# Pin-with-a-screen-3v3.net
KiCad netlist of a schematic drawn in EAGLE
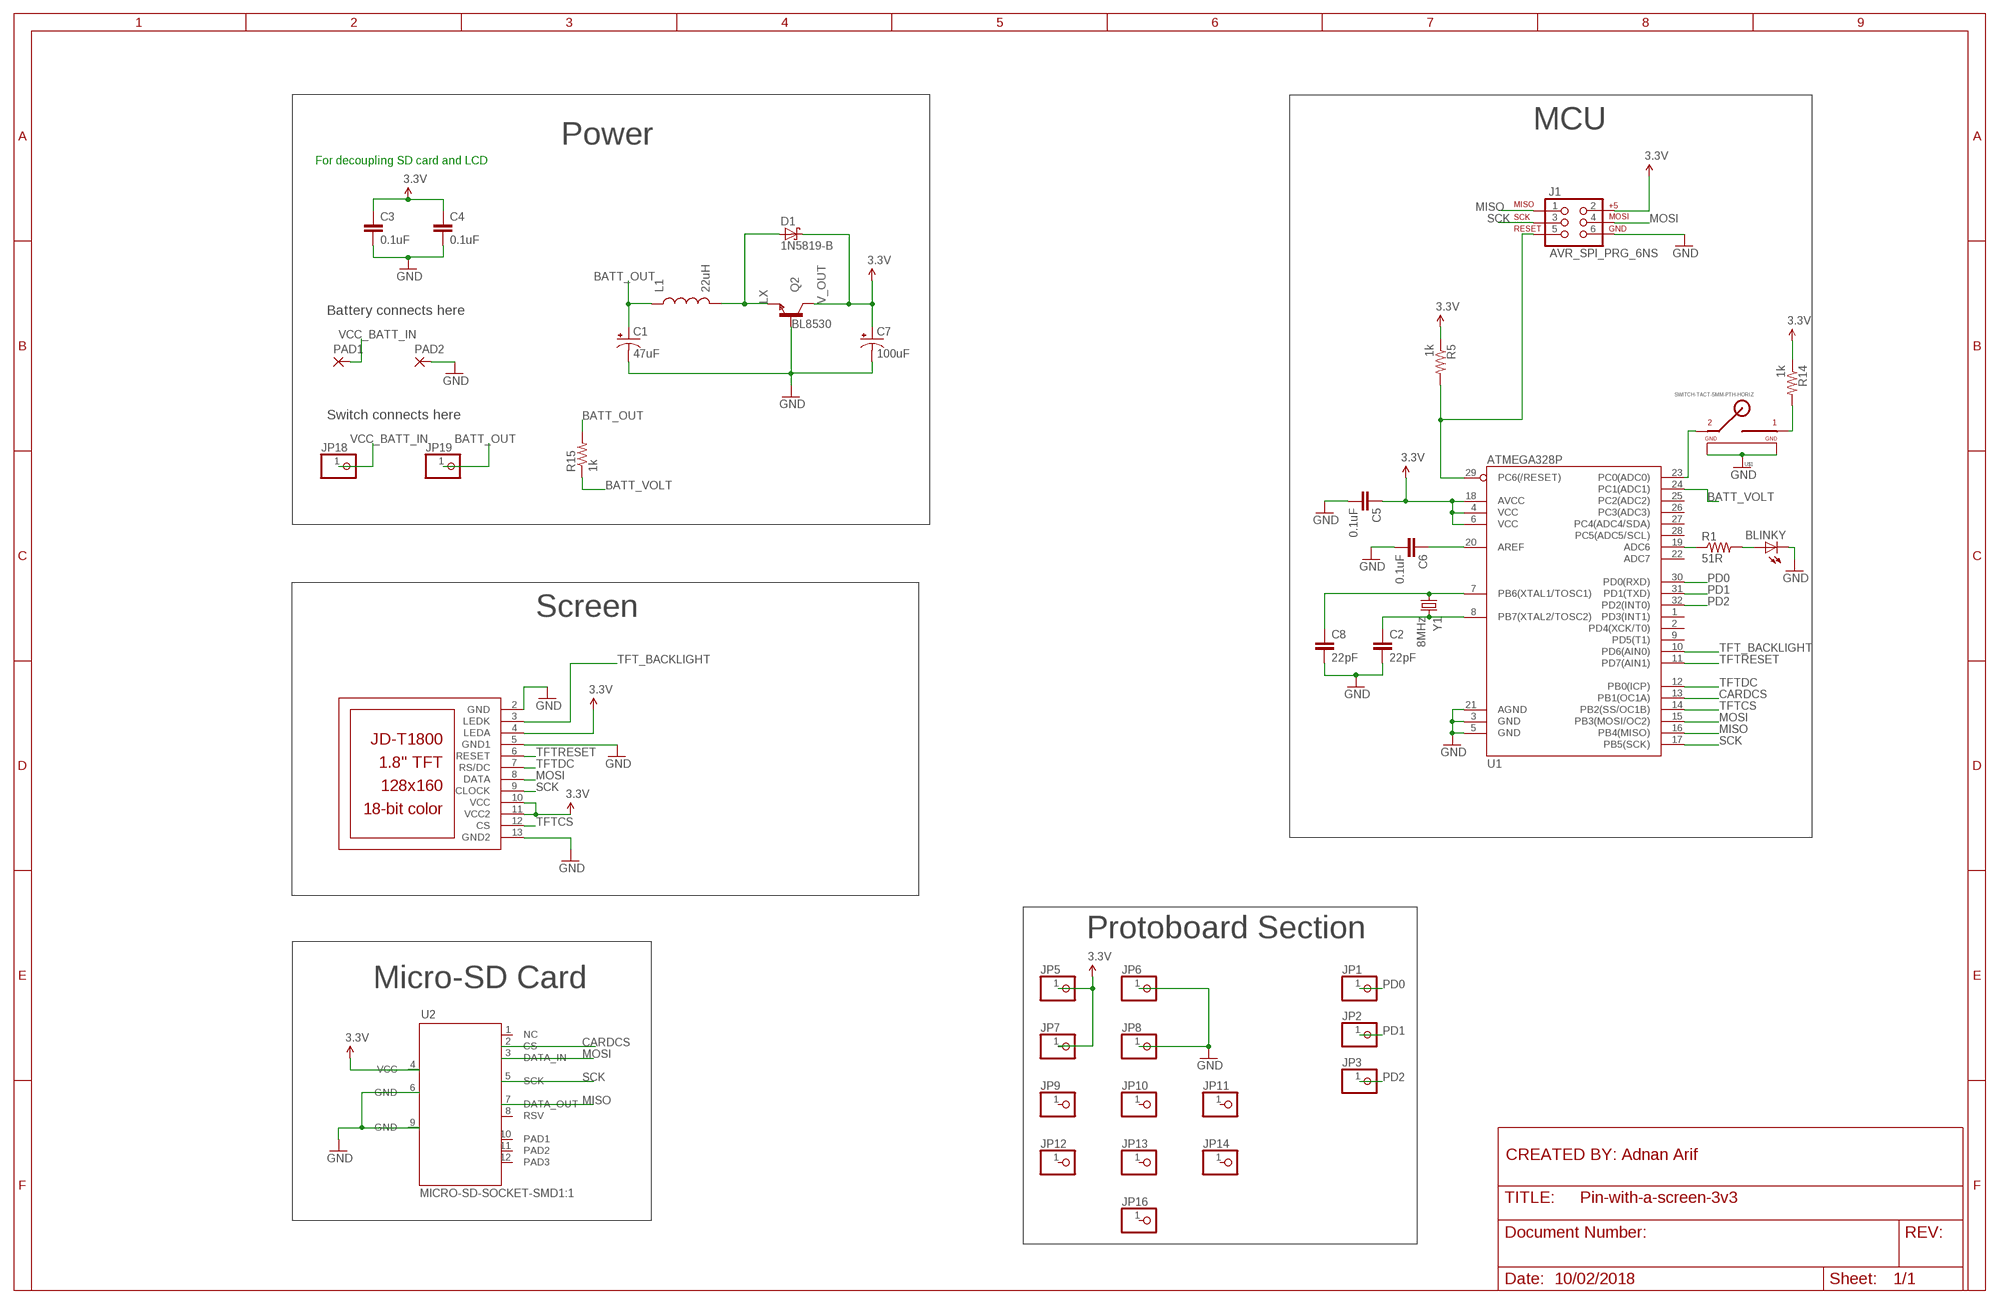
[diagram p0: schematic, sheet 1]

(export (version "E")
  (design (tool "Eeschema 10.0.6"))
  (components
    (comp (ref "BLINKY")
      (value "Red")
      (footprint "eagle-import:LED-0603")
      (libsource (lib "eagle-import") (part "LED0603"))
    )
    (comp (ref "C1")
      (value "47uF")
      (footprint "eagle-import:EIA3528-KIT")
      (libsource (lib "eagle-import") (part "CAP_POL3528-KIT"))
    )
    (comp (ref "C2")
      (value "22pF")
      (footprint "eagle-import:0603-CAP")
      (libsource (lib "eagle-import") (part "CAP0603-CAP"))
    )
    (comp (ref "C3")
      (value "0.1uF")
      (footprint "eagle-import:0603-CAP")
      (libsource (lib "eagle-import") (part "CAP0603-CAP"))
    )
    (comp (ref "C4")
      (value "0.1uF")
      (footprint "eagle-import:0603-CAP")
      (libsource (lib "eagle-import") (part "CAP0603-CAP"))
    )
    (comp (ref "C5")
      (value "0.1uF")
      (footprint "eagle-import:0603-CAP")
      (libsource (lib "eagle-import") (part "CAP0603-CAP"))
    )
    (comp (ref "C6")
      (value "0.1uF")
      (footprint "eagle-import:0603-CAP")
      (libsource (lib "eagle-import") (part "CAP0603-CAP"))
    )
    (comp (ref "C7")
      (value "100uF")
      (footprint "eagle-import:EIA3528-KIT")
      (libsource (lib "eagle-import") (part "CAP_POL3528-KIT"))
    )
    (comp (ref "C8")
      (value "22pF")
      (footprint "eagle-import:0603-CAP")
      (libsource (lib "eagle-import") (part "CAP0603-CAP"))
    )
    (comp (ref "D1")
      (value "1N5819-B")
      (footprint "eagle-import:DO41-7.6")
      (libsource (lib "eagle-import") (part "1N5819-B"))
    )
    (comp (ref "J1")
      (value "AVR_SPI_PRG_6NS")
      (footprint "eagle-import:2X3-NS")
      (libsource (lib "eagle-import") (part "AVR_SPI_PRG_6NS"))
    )
    (comp (ref "JP1")
      (value "PINHD-1X1")
      (footprint "eagle-import:1X01")
      (libsource (lib "eagle-import") (part "PINHD-1X1"))
    )
    (comp (ref "JP2")
      (value "PINHD-1X1")
      (footprint "eagle-import:1X01")
      (libsource (lib "eagle-import") (part "PINHD-1X1"))
    )
    (comp (ref "JP3")
      (value "PINHD-1X1")
      (footprint "eagle-import:1X01")
      (libsource (lib "eagle-import") (part "PINHD-1X1"))
    )
    (comp (ref "JP5")
      (value "PINHD-1X1")
      (footprint "eagle-import:1X01")
      (libsource (lib "eagle-import") (part "PINHD-1X1"))
    )
    (comp (ref "JP6")
      (value "PINHD-1X1")
      (footprint "eagle-import:1X01")
      (libsource (lib "eagle-import") (part "PINHD-1X1"))
    )
    (comp (ref "JP7")
      (value "PINHD-1X1")
      (footprint "eagle-import:1X01")
      (libsource (lib "eagle-import") (part "PINHD-1X1"))
    )
    (comp (ref "JP8")
      (value "PINHD-1X1")
      (footprint "eagle-import:1X01")
      (libsource (lib "eagle-import") (part "PINHD-1X1"))
    )
    (comp (ref "JP9")
      (value "PINHD-1X1")
      (footprint "eagle-import:1X01")
      (libsource (lib "eagle-import") (part "PINHD-1X1"))
    )
    (comp (ref "JP10")
      (value "PINHD-1X1")
      (footprint "eagle-import:1X01")
      (libsource (lib "eagle-import") (part "PINHD-1X1"))
    )
    (comp (ref "JP11")
      (value "PINHD-1X1")
      (footprint "eagle-import:1X01")
      (libsource (lib "eagle-import") (part "PINHD-1X1"))
    )
    (comp (ref "JP12")
      (value "PINHD-1X1")
      (footprint "eagle-import:1X01")
      (libsource (lib "eagle-import") (part "PINHD-1X1"))
    )
    (comp (ref "JP13")
      (value "PINHD-1X1")
      (footprint "eagle-import:1X01")
      (libsource (lib "eagle-import") (part "PINHD-1X1"))
    )
    (comp (ref "JP14")
      (value "PINHD-1X1")
      (footprint "eagle-import:1X01")
      (libsource (lib "eagle-import") (part "PINHD-1X1"))
    )
    (comp (ref "JP16")
      (value "PINHD-1X1")
      (footprint "eagle-import:1X01")
      (libsource (lib "eagle-import") (part "PINHD-1X1"))
    )
    (comp (ref "JP18")
      (value "PINHD-1X1")
      (footprint "eagle-import:1X01")
      (libsource (lib "eagle-import") (part "PINHD-1X1"))
    )
    (comp (ref "JP19")
      (value "PINHD-1X1")
      (footprint "eagle-import:1X01")
      (libsource (lib "eagle-import") (part "PINHD-1X1"))
    )
    (comp (ref "L1")
      (value "22uH")
      (footprint "eagle-import:0603")
      (libsource (lib "eagle-import") (part "INDUCTOR0603"))
    )
    (comp (ref "LCD2")
      (value "JD-T1800")
      (footprint "eagle-import:JD-T1800")
      (libsource (lib "eagle-import") (part "JD-T1800"))
    )
    (comp (ref "PAD1")
      (value "2,15/1,0")
      (footprint "eagle-import:2,15_1,0")
      (libsource (lib "eagle-import") (part "2,15/1,0"))
    )
    (comp (ref "PAD2")
      (value "2,15/1,0")
      (footprint "eagle-import:2,15_1,0")
      (libsource (lib "eagle-import") (part "2,15/1,0"))
    )
    (comp (ref "Q2")
      (value "BL8530")
      (footprint "eagle-import:SOT89")
      (libsource (lib "eagle-import") (part "TRANSISTOR_NPNSOT89"))
    )
    (comp (ref "R1")
      (value "51R")
      (footprint "eagle-import:0603-RES")
      (libsource (lib "eagle-import") (part "RESISTOR0603-RES"))
    )
    (comp (ref "R5")
      (value "1k")
      (footprint "eagle-import:0603-RES")
      (libsource (lib "eagle-import") (part "RESISTOR0603-RES"))
    )
    (comp (ref "R14")
      (value "1k")
      (footprint "eagle-import:0603-RES")
      (libsource (lib "eagle-import") (part "RESISTOR0603-RES"))
    )
    (comp (ref "R15")
      (value "1k")
      (footprint "eagle-import:0603-RES")
      (libsource (lib "eagle-import") (part "RESISTOR0603-RES"))
    )
    (comp (ref "U$1")
      (value "SWITCH-TACT-5MM-PTH-HORIZ")
      (footprint "eagle-import:5MM-PTH")
      (libsource (lib "eagle-import") (part "SWITCH-TACT-5MM-PTH-HORIZ"))
    )
    (comp (ref "U1")
      (value "ATMEGA328P")
      (footprint "eagle-import:TQFP32-08")
      (libsource (lib "eagle-import") (part "ATMEGA328_SMT"))
    )
    (comp (ref "U2")
      (value "MICRO-SD-SOCKET-SMD1:1")
      (footprint "eagle-import:MICRO-SD-SOCKET-SMD-1_1")
      (libsource (lib "eagle-import") (part "MICRO-SD-SOCKET-SMD1{colon}1"))
    )
    (comp (ref "Y1")
      (value "8MHz")
      (footprint "eagle-import:HC49UP")
      (libsource (lib "eagle-import") (part "CRYSTALSMD"))
    )
  )
  (nets
    (net (code "1") (name "/BATT_OUT") (class "Default")
      (node (ref "C1") (pin "A") (pinfunction "+_A") (pintype "passive"))
      (node (ref "JP19") (pin "1") (pinfunction "1_1") (pintype "passive"))
      (node (ref "L1") (pin "1") (pinfunction "1_1") (pintype "passive"))
      (node (ref "R15") (pin "2") (pinfunction "2_2") (pintype "passive"))
    )
    (net (code "2") (name "/BATT_VOLT") (class "Default")
      (node (ref "R15") (pin "1") (pinfunction "1_1") (pintype "passive"))
      (node (ref "U1") (pin "24") (pinfunction "PC1(ADC1)_24") (pintype "bidirectional"))
    )
    (net (code "3") (name "/CARDCS") (class "Default")
      (node (ref "U1") (pin "13") (pinfunction "PB1(OC1A)_13") (pintype "bidirectional"))
      (node (ref "U2") (pin "2") (pinfunction "CS_2") (pintype "input"))
    )
    (net (code "4") (name "/LX") (class "Default")
      (node (ref "D1") (pin "A") (pinfunction "A_A") (pintype "passive"))
      (node (ref "L1") (pin "2") (pinfunction "2_2") (pintype "passive"))
      (node (ref "Q2") (pin "3") (pinfunction "E_3") (pintype "passive"))
    )
    (net (code "5") (name "/MISO") (class "Default")
      (node (ref "J1") (pin "1") (pinfunction "1_1") (pintype "passive"))
      (node (ref "U1") (pin "16") (pinfunction "PB4(MISO)_16") (pintype "bidirectional"))
      (node (ref "U2") (pin "7") (pinfunction "DATA_OUT_7") (pintype "output"))
    )
    (net (code "6") (name "/MOSI") (class "Default")
      (node (ref "J1") (pin "4") (pinfunction "4_4") (pintype "passive"))
      (node (ref "LCD2") (pin "8") (pinfunction "DATA_8") (pintype "bidirectional"))
      (node (ref "U1") (pin "15") (pinfunction "PB3(MOSI/OC2)_15") (pintype "bidirectional"))
      (node (ref "U2") (pin "3") (pinfunction "DATA_IN_3") (pintype "input"))
    )
    (net (code "7") (name "/PD0") (class "Default")
      (node (ref "JP1") (pin "1") (pinfunction "1_1") (pintype "passive"))
      (node (ref "U1") (pin "30") (pinfunction "PD0(RXD)_30") (pintype "bidirectional"))
    )
    (net (code "8") (name "/PD1") (class "Default")
      (node (ref "JP2") (pin "1") (pinfunction "1_1") (pintype "passive"))
      (node (ref "U1") (pin "31") (pinfunction "PD1(TXD)_31") (pintype "bidirectional"))
    )
    (net (code "9") (name "/PD2") (class "Default")
      (node (ref "JP3") (pin "1") (pinfunction "1_1") (pintype "passive"))
      (node (ref "U1") (pin "32") (pinfunction "PD2(INT0)_32") (pintype "bidirectional"))
    )
    (net (code "10") (name "/SCK") (class "Default")
      (node (ref "J1") (pin "3") (pinfunction "3_3") (pintype "passive"))
      (node (ref "LCD2") (pin "9") (pinfunction "CLOCK_9") (pintype "input"))
      (node (ref "U1") (pin "17") (pinfunction "PB5(SCK)_17") (pintype "bidirectional"))
      (node (ref "U2") (pin "5") (pinfunction "SCK_5") (pintype "input"))
    )
    (net (code "11") (name "/TFTCS") (class "Default")
      (node (ref "LCD2") (pin "12") (pinfunction "CS_12") (pintype "input"))
      (node (ref "U1") (pin "14") (pinfunction "PB2(SS/OC1B)_14") (pintype "bidirectional"))
    )
    (net (code "12") (name "/TFTDC") (class "Default")
      (node (ref "LCD2") (pin "7") (pinfunction "RS/DC_7") (pintype "input"))
      (node (ref "U1") (pin "12") (pinfunction "PB0(ICP)_12") (pintype "bidirectional"))
    )
    (net (code "13") (name "/TFTRESET") (class "Default")
      (node (ref "LCD2") (pin "6") (pinfunction "RESET_6") (pintype "input"))
      (node (ref "U1") (pin "11") (pinfunction "PD7(AIN1)_11") (pintype "bidirectional"))
    )
    (net (code "14") (name "/TFT_BACKLIGHT") (class "Default")
      (node (ref "LCD2") (pin "3") (pinfunction "LEDK_3") (pintype "input"))
      (node (ref "U1") (pin "10") (pinfunction "PD6(AIN0)_10") (pintype "bidirectional"))
    )
    (net (code "15") (name "/VCC_BATT_IN") (class "Default")
      (node (ref "JP18") (pin "1") (pinfunction "1_1") (pintype "passive"))
      (node (ref "PAD1") (pin "1") (pinfunction "P_1") (pintype "passive"))
    )
    (net (code "16") (name "3.3V") (class "Default")
      (node (ref "C3") (pin "1") (pinfunction "1_1") (pintype "passive"))
      (node (ref "C4") (pin "1") (pinfunction "1_1") (pintype "passive"))
      (node (ref "C5") (pin "1") (pinfunction "1_1") (pintype "passive"))
      (node (ref "C7") (pin "A") (pinfunction "+_A") (pintype "passive"))
      (node (ref "D1") (pin "C") (pinfunction "C_C") (pintype "passive"))
      (node (ref "J1") (pin "2") (pinfunction "2_2") (pintype "passive"))
      (node (ref "JP5") (pin "1") (pinfunction "1_1") (pintype "passive"))
      (node (ref "JP7") (pin "1") (pinfunction "1_1") (pintype "passive"))
      (node (ref "LCD2") (pin "10") (pinfunction "VCC_10") (pintype "power_in"))
      (node (ref "LCD2") (pin "11") (pinfunction "VCC2_11") (pintype "power_in"))
      (node (ref "LCD2") (pin "4") (pinfunction "LEDA_4") (pintype "input"))
      (node (ref "Q2") (pin "2") (pinfunction "C_2") (pintype "passive"))
      (node (ref "R14") (pin "1") (pinfunction "1_1") (pintype "passive"))
      (node (ref "R5") (pin "1") (pinfunction "1_1") (pintype "passive"))
      (node (ref "U1") (pin "18") (pinfunction "AVCC_18") (pintype "bidirectional"))
      (node (ref "U1") (pin "4") (pinfunction "VCC_4") (pintype "bidirectional"))
      (node (ref "U1") (pin "6") (pinfunction "VCC_6") (pintype "bidirectional"))
      (node (ref "U2") (pin "4") (pinfunction "VCC_4") (pintype "power_in"))
    )
    (net (code "17") (name "GND") (class "Default")
      (node (ref "BLINKY") (pin "C") (pinfunction "C_C") (pintype "passive"))
      (node (ref "C1") (pin "C") (pinfunction "-_C") (pintype "passive"))
      (node (ref "C2") (pin "2") (pinfunction "2_2") (pintype "passive"))
      (node (ref "C3") (pin "2") (pinfunction "2_2") (pintype "passive"))
      (node (ref "C4") (pin "2") (pinfunction "2_2") (pintype "passive"))
      (node (ref "C5") (pin "2") (pinfunction "2_2") (pintype "passive"))
      (node (ref "C6") (pin "2") (pinfunction "2_2") (pintype "passive"))
      (node (ref "C7") (pin "C") (pinfunction "-_C") (pintype "passive"))
      (node (ref "C8") (pin "2") (pinfunction "2_2") (pintype "passive"))
      (node (ref "J1") (pin "6") (pinfunction "6_6") (pintype "passive"))
      (node (ref "JP6") (pin "1") (pinfunction "1_1") (pintype "passive"))
      (node (ref "JP8") (pin "1") (pinfunction "1_1") (pintype "passive"))
      (node (ref "LCD2") (pin "13") (pinfunction "GND2_13") (pintype "power_in"))
      (node (ref "LCD2") (pin "2") (pinfunction "GND_2") (pintype "power_in"))
      (node (ref "LCD2") (pin "5") (pinfunction "GND1_5") (pintype "power_in"))
      (node (ref "PAD2") (pin "1") (pinfunction "P_1") (pintype "passive"))
      (node (ref "Q2") (pin "1") (pinfunction "B_1") (pintype "passive"))
      (node (ref "U$1") (pin "GND") (pinfunction "GND_GND") (pintype "power_in"))
      (node (ref "U$1") (pin "GND1") (pinfunction "GND1_GND1") (pintype "power_in"))
      (node (ref "U1") (pin "21") (pinfunction "AGND_21") (pintype "bidirectional"))
      (node (ref "U1") (pin "3") (pinfunction "GND_3") (pintype "bidirectional"))
      (node (ref "U1") (pin "5") (pinfunction "GND_5") (pintype "bidirectional"))
      (node (ref "U2") (pin "6") (pinfunction "GND_6") (pintype "power_in"))
      (node (ref "U2") (pin "9") (pinfunction "GND_9") (pintype "power_in"))
    )
    (net (code "18") (name "Net-(BLINKY-PadA)") (class "Default")
      (node (ref "BLINKY") (pin "A") (pinfunction "A_A") (pintype "passive"))
      (node (ref "R1") (pin "2") (pinfunction "2_2") (pintype "passive"))
    )
    (net (code "19") (name "Net-(R14-Pad2)") (class "Default")
      (node (ref "R14") (pin "2") (pinfunction "2_2") (pintype "passive"))
      (node (ref "U$1") (pin "1") (pinfunction "1_1") (pintype "bidirectional"))
    )
    (net (code "20") (name "Net-(U1-ADC6)") (class "Default")
      (node (ref "R1") (pin "1") (pinfunction "1_1") (pintype "passive"))
      (node (ref "U1") (pin "19") (pinfunction "ADC6_19") (pintype "bidirectional"))
    )
    (net (code "21") (name "Net-(U1-AREF)") (class "Default")
      (node (ref "C6") (pin "1") (pinfunction "1_1") (pintype "passive"))
      (node (ref "U1") (pin "20") (pinfunction "AREF_20") (pintype "bidirectional"))
    )
    (net (code "22") (name "Net-(U1-PB6(XTAL1{slash}TOSC1))") (class "Default")
      (node (ref "C8") (pin "1") (pinfunction "1_1") (pintype "passive"))
      (node (ref "U1") (pin "7") (pinfunction "PB6(XTAL1/TOSC1)_7") (pintype "bidirectional"))
      (node (ref "Y1") (pin "1") (pinfunction "1_1") (pintype "passive"))
    )
    (net (code "23") (name "Net-(U1-PB7(XTAL2{slash}TOSC2))") (class "Default")
      (node (ref "C2") (pin "1") (pinfunction "1_1") (pintype "passive"))
      (node (ref "U1") (pin "8") (pinfunction "PB7(XTAL2/TOSC2)_8") (pintype "bidirectional"))
      (node (ref "Y1") (pin "2") (pinfunction "2_2") (pintype "passive"))
    )
    (net (code "24") (name "Net-(U1-PC0(ADC0))") (class "Default")
      (node (ref "U$1") (pin "2") (pinfunction "2_2") (pintype "bidirectional"))
      (node (ref "U1") (pin "23") (pinfunction "PC0(ADC0)_23") (pintype "bidirectional"))
    )
    (net (code "25") (name "Net-(U1-PC6({slash}RESET))") (class "Default")
      (node (ref "J1") (pin "5") (pinfunction "5_5") (pintype "passive"))
      (node (ref "R5") (pin "2") (pinfunction "2_2") (pintype "passive"))
      (node (ref "U1") (pin "29") (pinfunction "PC6(/RESET)_29") (pintype "bidirectional"))
    )
    (net (code "26") (name "unconnected-(JP9-Pad1)") (class "Default")
      (node (ref "JP9") (pin "1") (pinfunction "1_1") (pintype "passive"))
    )
    (net (code "27") (name "unconnected-(JP10-Pad1)") (class "Default")
      (node (ref "JP10") (pin "1") (pinfunction "1_1") (pintype "passive"))
    )
    (net (code "28") (name "unconnected-(JP11-Pad1)") (class "Default")
      (node (ref "JP11") (pin "1") (pinfunction "1_1") (pintype "passive"))
    )
    (net (code "29") (name "unconnected-(JP12-Pad1)") (class "Default")
      (node (ref "JP12") (pin "1") (pinfunction "1_1") (pintype "passive"))
    )
    (net (code "30") (name "unconnected-(JP13-Pad1)") (class "Default")
      (node (ref "JP13") (pin "1") (pinfunction "1_1") (pintype "passive"))
    )
    (net (code "31") (name "unconnected-(JP14-Pad1)") (class "Default")
      (node (ref "JP14") (pin "1") (pinfunction "1_1") (pintype "passive"))
    )
    (net (code "32") (name "unconnected-(JP16-Pad1)") (class "Default")
      (node (ref "JP16") (pin "1") (pinfunction "1_1") (pintype "passive"))
    )
    (net (code "33") (name "unconnected-(U1-ADC7-Pad22)") (class "Default")
      (node (ref "U1") (pin "22") (pinfunction "ADC7_22") (pintype "bidirectional"))
    )
    (net (code "34") (name "unconnected-(U1-PC2(ADC2)-Pad25)") (class "Default")
      (node (ref "U1") (pin "25") (pinfunction "PC2(ADC2)_25") (pintype "bidirectional"))
    )
    (net (code "35") (name "unconnected-(U1-PC3(ADC3)-Pad26)") (class "Default")
      (node (ref "U1") (pin "26") (pinfunction "PC3(ADC3)_26") (pintype "bidirectional"))
    )
    (net (code "36") (name "unconnected-(U1-PC4(ADC4{slash}SDA)-Pad27)") (class "Default")
      (node (ref "U1") (pin "27") (pinfunction "PC4(ADC4/SDA)_27") (pintype "bidirectional"))
    )
    (net (code "37") (name "unconnected-(U1-PC5(ADC5{slash}SCL)-Pad28)") (class "Default")
      (node (ref "U1") (pin "28") (pinfunction "PC5(ADC5/SCL)_28") (pintype "bidirectional"))
    )
    (net (code "38") (name "unconnected-(U1-PD3(INT1)-Pad1)") (class "Default")
      (node (ref "U1") (pin "1") (pinfunction "PD3(INT1)_1") (pintype "bidirectional"))
    )
    (net (code "39") (name "unconnected-(U1-PD4(XCK{slash}T0)-Pad2)") (class "Default")
      (node (ref "U1") (pin "2") (pinfunction "PD4(XCK/T0)_2") (pintype "bidirectional"))
    )
    (net (code "40") (name "unconnected-(U1-PD5(T1)-Pad9)") (class "Default")
      (node (ref "U1") (pin "9") (pinfunction "PD5(T1)_9") (pintype "bidirectional"))
    )
    (net (code "41") (name "unconnected-(U2-NC-Pad1)") (class "Default")
      (node (ref "U2") (pin "1") (pinfunction "NC_1") (pintype "no_connect"))
    )
    (net (code "42") (name "unconnected-(U2-PAD1-Pad10)") (class "Default")
      (node (ref "U2") (pin "10") (pinfunction "PAD1_10") (pintype "bidirectional"))
    )
    (net (code "43") (name "unconnected-(U2-PAD2-Pad11)") (class "Default")
      (node (ref "U2") (pin "11") (pinfunction "PAD2_11") (pintype "bidirectional"))
    )
    (net (code "44") (name "unconnected-(U2-PAD3-Pad12)") (class "Default")
      (node (ref "U2") (pin "12") (pinfunction "PAD3_12") (pintype "bidirectional"))
    )
    (net (code "45") (name "unconnected-(U2-RSV-Pad8)") (class "Default")
      (node (ref "U2") (pin "8") (pinfunction "RSV_8") (pintype "bidirectional"))
    )
  )
)
